# testv2.net
KiCad netlist of a schematic drawn in EAGLE
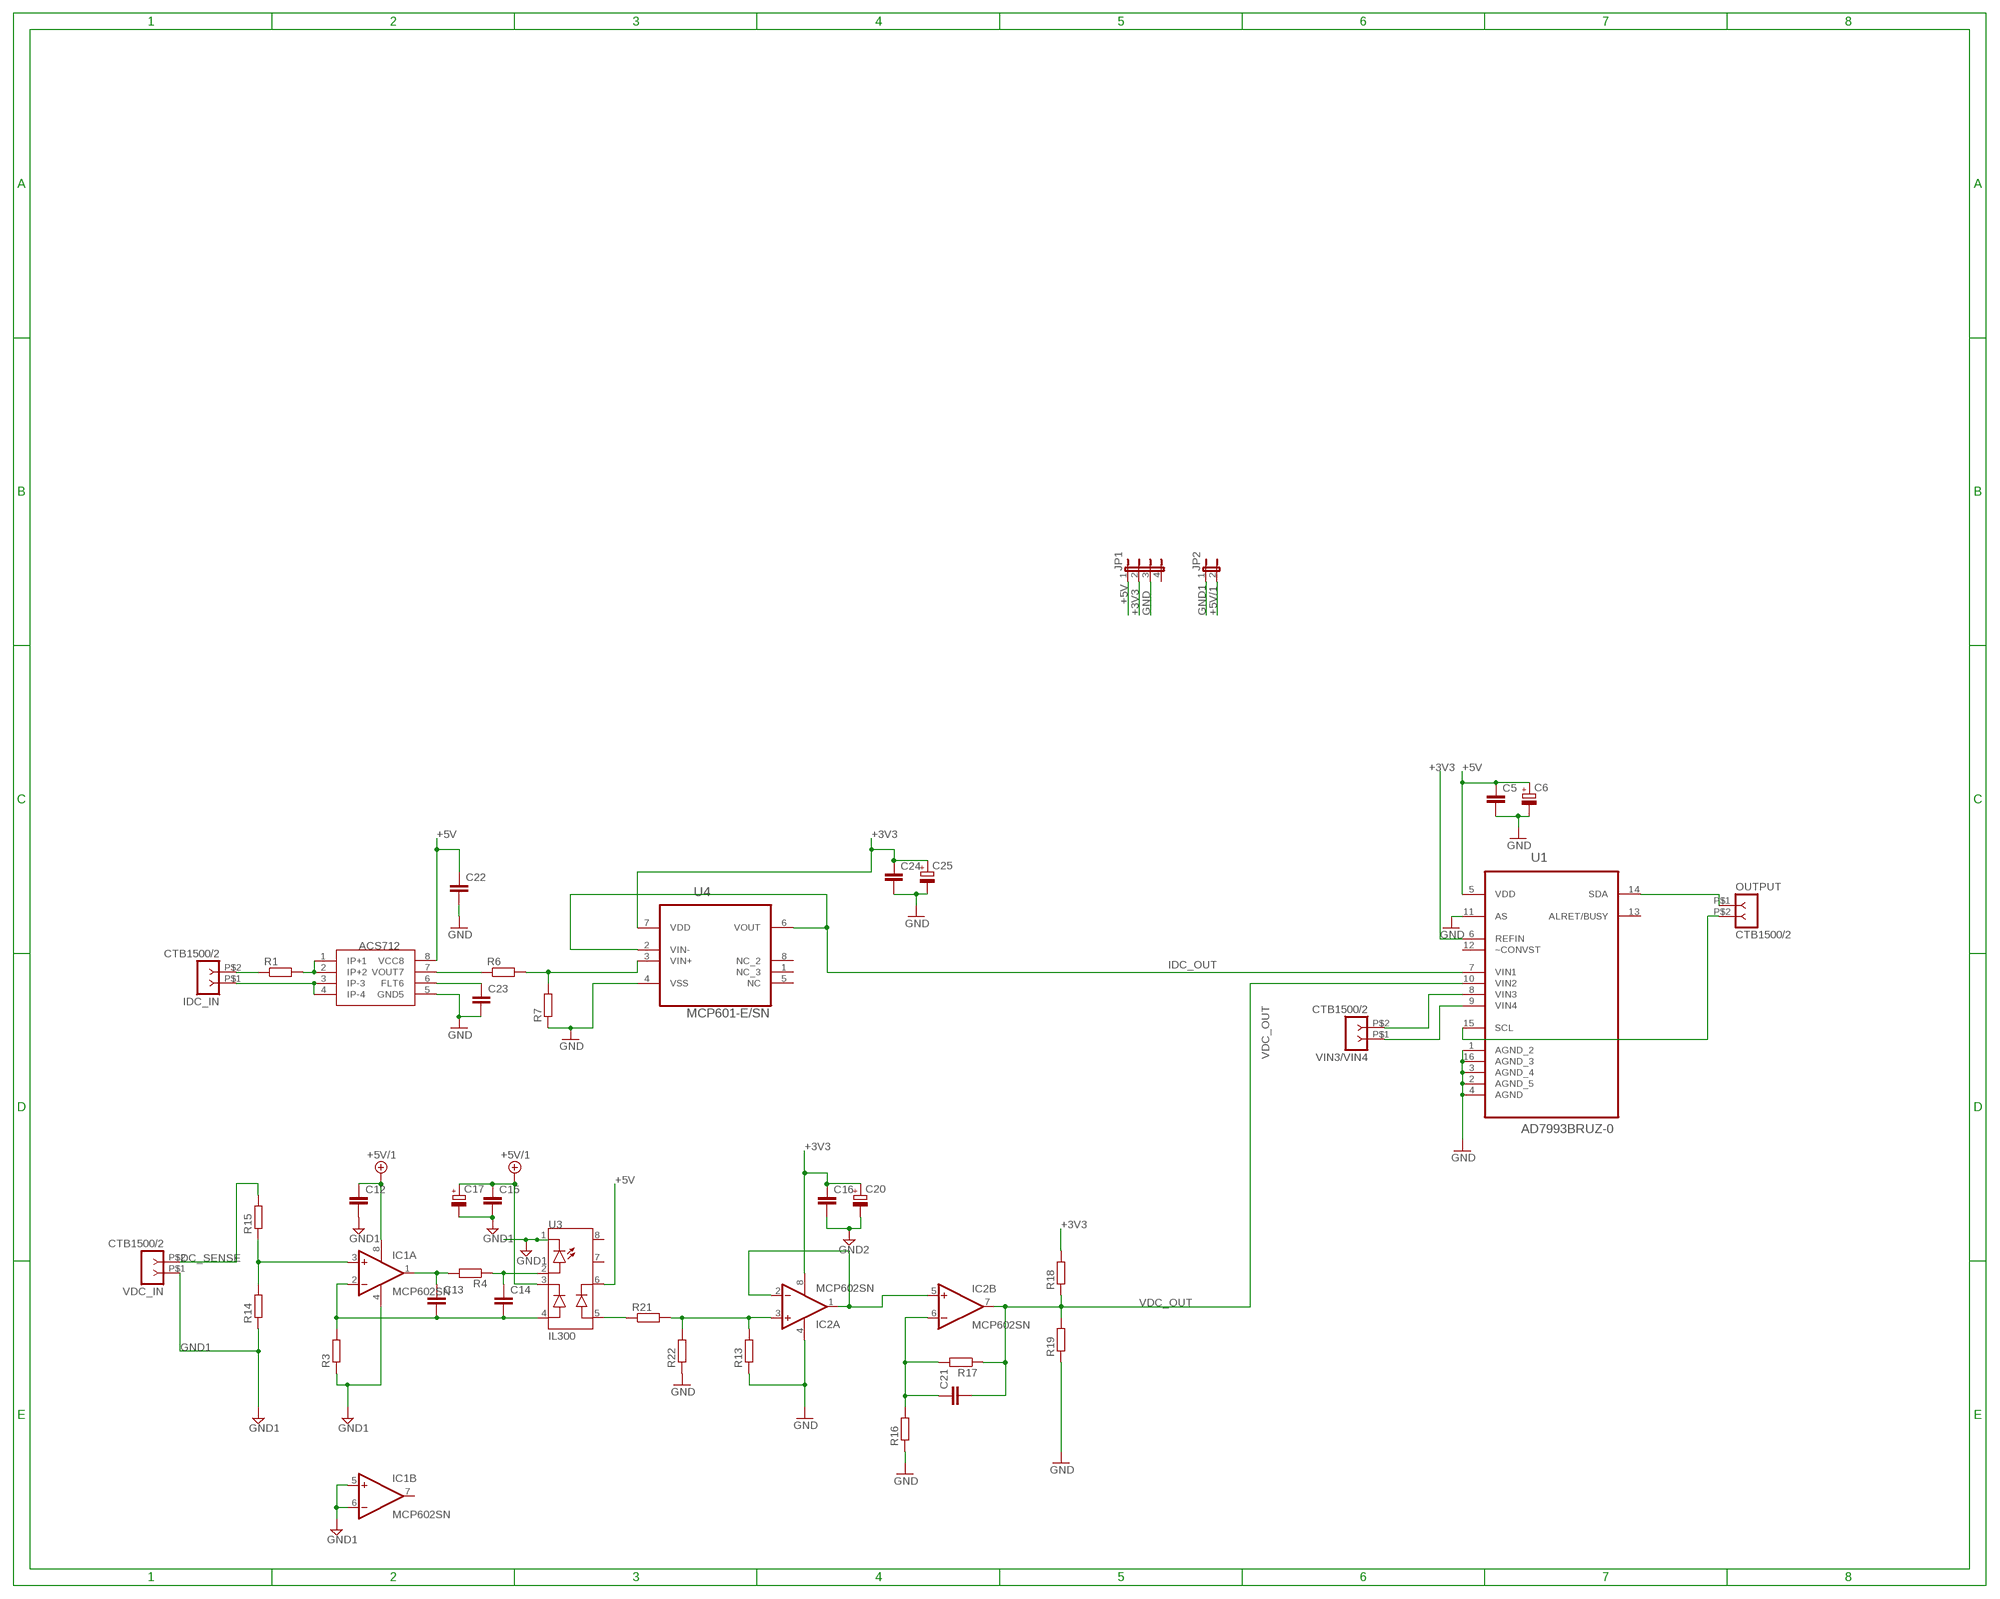
[diagram p0: schematic, sheet 1]

(export (version "E")
  (design (tool "Eeschema 10.0.6"))
  (components
    (comp (ref "C5")
      (value "C-EU025-025X050")
      (footprint "eagle-import:C025-025X050")
      (libsource (lib "eagle-import") (part "C-EU025-025X050"))
    )
    (comp (ref "C6")
      (value "CPOL-EUE2-4")
      (footprint "eagle-import:E2-4")
      (libsource (lib "eagle-import") (part "CPOL-EUE2-4"))
    )
    (comp (ref "C12")
      (value "C-EU025-025X050")
      (footprint "eagle-import:C025-025X050")
      (libsource (lib "eagle-import") (part "C-EU025-025X050"))
    )
    (comp (ref "C13")
      (value "C-EU025-025X050")
      (footprint "eagle-import:C025-025X050")
      (libsource (lib "eagle-import") (part "C-EU025-025X050"))
    )
    (comp (ref "C14")
      (value "C-EU025-025X050")
      (footprint "eagle-import:C025-025X050")
      (libsource (lib "eagle-import") (part "C-EU025-025X050"))
    )
    (comp (ref "C15")
      (value "C-EU025-025X050")
      (footprint "eagle-import:C025-025X050")
      (libsource (lib "eagle-import") (part "C-EU025-025X050"))
    )
    (comp (ref "C16")
      (value "C-EU025-025X050")
      (footprint "eagle-import:C025-025X050")
      (libsource (lib "eagle-import") (part "C-EU025-025X050"))
    )
    (comp (ref "C17")
      (value "CPOL-EUE2-4")
      (footprint "eagle-import:E2-4")
      (libsource (lib "eagle-import") (part "CPOL-EUE2-4"))
    )
    (comp (ref "C20")
      (value "CPOL-EUE2-4")
      (footprint "eagle-import:E2-4")
      (libsource (lib "eagle-import") (part "CPOL-EUE2-4"))
    )
    (comp (ref "C21")
      (value "C-EU025-025X050")
      (footprint "eagle-import:C025-025X050")
      (libsource (lib "eagle-import") (part "C-EU025-025X050"))
    )
    (comp (ref "C22")
      (value "C-EU025-025X050")
      (footprint "eagle-import:C025-025X050")
      (libsource (lib "eagle-import") (part "C-EU025-025X050"))
    )
    (comp (ref "C23")
      (value "C-EU025-025X050")
      (footprint "eagle-import:C025-025X050")
      (libsource (lib "eagle-import") (part "C-EU025-025X050"))
    )
    (comp (ref "C24")
      (value "C-EU025-025X050")
      (footprint "eagle-import:C025-025X050")
      (libsource (lib "eagle-import") (part "C-EU025-025X050"))
    )
    (comp (ref "C25")
      (value "CPOL-EUE2-4")
      (footprint "eagle-import:E2-4")
      (libsource (lib "eagle-import") (part "CPOL-EUE2-4"))
    )
    (comp (ref "IC1")
      (value "MCP602SN")
      (footprint "eagle-import:SO08")
      (libsource (lib "eagle-import") (part "MCP602SN"))
    )
    (comp (ref "IC2")
      (value "MCP602SN")
      (footprint "eagle-import:SO08")
      (libsource (lib "eagle-import") (part "MCP602SN"))
    )
    (comp (ref "IDC_IN")
      (value "CTB1500/2")
      (footprint "eagle-import:CTB1500-2")
      (libsource (lib "eagle-import") (part "CTB1500/2"))
    )
    (comp (ref "JP1")
      (value "JP4E")
      (footprint "eagle-import:JP4")
      (libsource (lib "eagle-import") (part "JP4E"))
    )
    (comp (ref "JP2")
      (value "JP1E")
      (footprint "eagle-import:JP1")
      (libsource (lib "eagle-import") (part "JP1E"))
    )
    (comp (ref "OUTPUT")
      (value "CTB1500/2")
      (footprint "eagle-import:CTB1500-2")
      (libsource (lib "eagle-import") (part "CTB1500/2"))
    )
    (comp (ref "R1")
      (value "R-EU_0207/7")
      (footprint "eagle-import:0207_7")
      (libsource (lib "eagle-import") (part "R-EU_0207/7"))
    )
    (comp (ref "R3")
      (value "R-EU_0207/7")
      (footprint "eagle-import:0207_7")
      (libsource (lib "eagle-import") (part "R-EU_0207/7"))
    )
    (comp (ref "R4")
      (value "R-EU_0207/7")
      (footprint "eagle-import:0207_7")
      (libsource (lib "eagle-import") (part "R-EU_0207/7"))
    )
    (comp (ref "R6")
      (value "R-EU_0207/7")
      (footprint "eagle-import:0207_7")
      (libsource (lib "eagle-import") (part "R-EU_0207/7"))
    )
    (comp (ref "R7")
      (value "R-EU_0207/7")
      (footprint "eagle-import:0207_7")
      (libsource (lib "eagle-import") (part "R-EU_0207/7"))
    )
    (comp (ref "R13")
      (value "R-EU_0207/7")
      (footprint "eagle-import:0207_7")
      (libsource (lib "eagle-import") (part "R-EU_0207/7"))
    )
    (comp (ref "R14")
      (value "R-EU_0207/7")
      (footprint "eagle-import:0207_7")
      (libsource (lib "eagle-import") (part "R-EU_0207/7"))
    )
    (comp (ref "R15")
      (value "R-EU_0207/7")
      (footprint "eagle-import:0207_7")
      (libsource (lib "eagle-import") (part "R-EU_0207/7"))
    )
    (comp (ref "R16")
      (value "R-EU_0207/7")
      (footprint "eagle-import:0207_7")
      (libsource (lib "eagle-import") (part "R-EU_0207/7"))
    )
    (comp (ref "R17")
      (value "R-EU_0207/7")
      (footprint "eagle-import:0207_7")
      (libsource (lib "eagle-import") (part "R-EU_0207/7"))
    )
    (comp (ref "R18")
      (value "R-EU_0207/7")
      (footprint "eagle-import:0207_7")
      (libsource (lib "eagle-import") (part "R-EU_0207/7"))
    )
    (comp (ref "R19")
      (value "R-EU_0207/7")
      (footprint "eagle-import:0207_7")
      (libsource (lib "eagle-import") (part "R-EU_0207/7"))
    )
    (comp (ref "R21")
      (value "R-EU_0207/7")
      (footprint "eagle-import:0207_7")
      (libsource (lib "eagle-import") (part "R-EU_0207/7"))
    )
    (comp (ref "R22")
      (value "R-EU_0207/7")
      (footprint "eagle-import:0207_7")
      (libsource (lib "eagle-import") (part "R-EU_0207/7"))
    )
    (comp (ref "U$10")
      (value "ACS712")
      (footprint "eagle-import:SOIC8")
      (libsource (lib "eagle-import") (part "ACS712"))
    )
    (comp (ref "U1")
      (value "AD7993BRUZ-0")
      (footprint "eagle-import:SOP65P640X120-16N")
      (libsource (lib "eagle-import") (part "AD7993BRUZ-0"))
    )
    (comp (ref "U3")
      (value "IL300")
      (footprint "eagle-import:SO8")
      (libsource (lib "eagle-import") (part "IL300"))
    )
    (comp (ref "U4")
      (value "MCP601-E/SN")
      (footprint "eagle-import:SOIC127P600X175-8N")
      (libsource (lib "eagle-import") (part "MCP601-E/SN"))
    )
    (comp (ref "VDC_IN")
      (value "CTB1500/2")
      (footprint "eagle-import:CTB1500-2")
      (libsource (lib "eagle-import") (part "CTB1500/2"))
    )
    (comp (ref "VIN3/VIN4")
      (value "CTB1500/2")
      (footprint "eagle-import:CTB1500-2")
      (libsource (lib "eagle-import") (part "CTB1500/2"))
    )
  )
  (nets
    (net (code "1") (name "+5V{slash}1") (class "Default")
      (node (ref "C12") (pin "1") (pinfunction "1_1") (pintype "passive"))
      (node (ref "C15") (pin "1") (pinfunction "1_1") (pintype "passive"))
      (node (ref "C17") (pin "+") (pinfunction "+_+") (pintype "passive"))
      (node (ref "IC1") (pin "8") (pinfunction "V+_8") (pintype "power_in"))
      (node (ref "JP2") (pin "2") (pinfunction "2_2") (pintype "passive"))
      (node (ref "U3") (pin "3") (pinfunction "C_FB_3") (pintype "passive"))
    )
    (net (code "2") (name "/+3V3") (class "Default")
      (node (ref "C16") (pin "1") (pinfunction "1_1") (pintype "passive"))
      (node (ref "C20") (pin "+") (pinfunction "+_+") (pintype "passive"))
      (node (ref "C24") (pin "1") (pinfunction "1_1") (pintype "passive"))
      (node (ref "C25") (pin "+") (pinfunction "+_+") (pintype "passive"))
      (node (ref "IC2") (pin "8") (pinfunction "V+_8") (pintype "power_in"))
      (node (ref "JP1") (pin "2") (pinfunction "2_2") (pintype "passive"))
      (node (ref "R18") (pin "2") (pinfunction "2_2") (pintype "passive"))
      (node (ref "U1") (pin "6") (pinfunction "REFIN_6") (pintype "input"))
      (node (ref "U4") (pin "7") (pinfunction "VDD_7") (pintype "power_in"))
    )
    (net (code "3") (name "/+5V") (class "Default")
      (node (ref "C22") (pin "1") (pinfunction "1_1") (pintype "passive"))
      (node (ref "C5") (pin "1") (pinfunction "1_1") (pintype "passive"))
      (node (ref "C6") (pin "+") (pinfunction "+_+") (pintype "passive"))
      (node (ref "JP1") (pin "1") (pinfunction "1_1") (pintype "passive"))
      (node (ref "U$10") (pin "8") (pinfunction "VCC8_8") (pintype "power_in"))
      (node (ref "U1") (pin "5") (pinfunction "VDD_5") (pintype "power_in"))
      (node (ref "U3") (pin "6") (pinfunction "C_OUT_6") (pintype "passive"))
    )
    (net (code "4") (name "/DC_SENSE") (class "Default")
      (node (ref "R15") (pin "2") (pinfunction "2_2") (pintype "passive"))
      (node (ref "VDC_IN") (pin "P$2") (pinfunction "2_P$2") (pintype "passive"))
    )
    (net (code "5") (name "/IDC_OUT") (class "Default")
      (node (ref "U1") (pin "7") (pinfunction "VIN1_7") (pintype "input"))
      (node (ref "U4") (pin "2") (pinfunction "VIN-_2") (pintype "input"))
      (node (ref "U4") (pin "6") (pinfunction "VOUT_6") (pintype "output"))
    )
    (net (code "6") (name "/VDC_OUT") (class "Default")
      (node (ref "C21") (pin "2") (pinfunction "2_2") (pintype "passive"))
      (node (ref "IC2") (pin "7") (pinfunction "OUT_7") (pintype "output"))
      (node (ref "R17") (pin "1") (pinfunction "1_1") (pintype "passive"))
      (node (ref "R18") (pin "1") (pinfunction "1_1") (pintype "passive"))
      (node (ref "R19") (pin "2") (pinfunction "2_2") (pintype "passive"))
      (node (ref "U1") (pin "10") (pinfunction "VIN2_10") (pintype "input"))
    )
    (net (code "7") (name "GND") (class "Default")
      (node (ref "C22") (pin "2") (pinfunction "2_2") (pintype "passive"))
      (node (ref "C23") (pin "2") (pinfunction "2_2") (pintype "passive"))
      (node (ref "C24") (pin "2") (pinfunction "2_2") (pintype "passive"))
      (node (ref "C25") (pin "-") (pinfunction "-_-") (pintype "passive"))
      (node (ref "C5") (pin "2") (pinfunction "2_2") (pintype "passive"))
      (node (ref "C6") (pin "-") (pinfunction "-_-") (pintype "passive"))
      (node (ref "IC2") (pin "4") (pinfunction "V-_4") (pintype "power_in"))
      (node (ref "JP1") (pin "3") (pinfunction "3_3") (pintype "passive"))
      (node (ref "R13") (pin "1") (pinfunction "1_1") (pintype "passive"))
      (node (ref "R16") (pin "1") (pinfunction "1_1") (pintype "passive"))
      (node (ref "R19") (pin "1") (pinfunction "1_1") (pintype "passive"))
      (node (ref "R22") (pin "1") (pinfunction "1_1") (pintype "passive"))
      (node (ref "R7") (pin "1") (pinfunction "1_1") (pintype "passive"))
      (node (ref "U$10") (pin "5") (pinfunction "GND5_5") (pintype "power_in"))
      (node (ref "U1") (pin "1") (pinfunction "AGND_2_1") (pintype "passive"))
      (node (ref "U1") (pin "11") (pinfunction "AS_11") (pintype "input"))
      (node (ref "U1") (pin "16") (pinfunction "AGND_3_16") (pintype "passive"))
      (node (ref "U1") (pin "2") (pinfunction "AGND_5_2") (pintype "passive"))
      (node (ref "U1") (pin "3") (pinfunction "AGND_4_3") (pintype "passive"))
      (node (ref "U1") (pin "4") (pinfunction "AGND_4") (pintype "passive"))
      (node (ref "U4") (pin "4") (pinfunction "VSS_4") (pintype "power_in"))
    )
    (net (code "8") (name "GND1") (class "Default")
      (node (ref "C12") (pin "2") (pinfunction "2_2") (pintype "passive"))
      (node (ref "C15") (pin "2") (pinfunction "2_2") (pintype "passive"))
      (node (ref "C17") (pin "-") (pinfunction "-_-") (pintype "passive"))
      (node (ref "IC1") (pin "4") (pinfunction "V-_4") (pintype "power_in"))
      (node (ref "IC1") (pin "5") (pinfunction "+IN_5") (pintype "input"))
      (node (ref "IC1") (pin "6") (pinfunction "-IN_6") (pintype "input"))
      (node (ref "JP2") (pin "1") (pinfunction "1_1") (pintype "passive"))
      (node (ref "R14") (pin "1") (pinfunction "1_1") (pintype "passive"))
      (node (ref "R3") (pin "1") (pinfunction "1_1") (pintype "passive"))
      (node (ref "U3") (pin "1") (pinfunction "C_LED_1") (pintype "passive"))
      (node (ref "VDC_IN") (pin "P$1") (pinfunction "1_P$1") (pintype "passive"))
    )
    (net (code "9") (name "GND2") (class "Default")
      (node (ref "C16") (pin "2") (pinfunction "2_2") (pintype "passive"))
      (node (ref "C20") (pin "-") (pinfunction "-_-") (pintype "passive"))
    )
    (net (code "10") (name "Net-(IC1A-+IN)") (class "Default")
      (node (ref "IC1") (pin "3") (pinfunction "+IN_3") (pintype "input"))
      (node (ref "R14") (pin "2") (pinfunction "2_2") (pintype "passive"))
      (node (ref "R15") (pin "1") (pinfunction "1_1") (pintype "passive"))
    )
    (net (code "11") (name "Net-(IC1A--IN)") (class "Default")
      (node (ref "C13") (pin "2") (pinfunction "2_2") (pintype "passive"))
      (node (ref "C14") (pin "2") (pinfunction "2_2") (pintype "passive"))
      (node (ref "IC1") (pin "2") (pinfunction "-IN_2") (pintype "input"))
      (node (ref "R3") (pin "2") (pinfunction "2_2") (pintype "passive"))
      (node (ref "U3") (pin "4") (pinfunction "A_FB_4") (pintype "passive"))
    )
    (net (code "12") (name "Net-(IC1A-OUT)") (class "Default")
      (node (ref "C13") (pin "1") (pinfunction "1_1") (pintype "passive"))
      (node (ref "IC1") (pin "1") (pinfunction "OUT_1") (pintype "output"))
      (node (ref "R4") (pin "2") (pinfunction "2_2") (pintype "passive"))
    )
    (net (code "13") (name "Net-(IC2A-+IN)") (class "Default")
      (node (ref "IC2") (pin "3") (pinfunction "+IN_3") (pintype "input"))
      (node (ref "R13") (pin "2") (pinfunction "2_2") (pintype "passive"))
      (node (ref "R21") (pin "2") (pinfunction "2_2") (pintype "passive"))
      (node (ref "R22") (pin "2") (pinfunction "2_2") (pintype "passive"))
    )
    (net (code "14") (name "Net-(IC2A--IN)") (class "Default")
      (node (ref "IC2") (pin "1") (pinfunction "OUT_1") (pintype "output"))
      (node (ref "IC2") (pin "2") (pinfunction "-IN_2") (pintype "input"))
      (node (ref "IC2") (pin "5") (pinfunction "+IN_5") (pintype "input"))
    )
    (net (code "15") (name "Net-(IC2B--IN)") (class "Default")
      (node (ref "C21") (pin "1") (pinfunction "1_1") (pintype "passive"))
      (node (ref "IC2") (pin "6") (pinfunction "-IN_6") (pintype "input"))
      (node (ref "R16") (pin "2") (pinfunction "2_2") (pintype "passive"))
      (node (ref "R17") (pin "2") (pinfunction "2_2") (pintype "passive"))
    )
    (net (code "16") (name "Net-(IDC_IN-1)") (class "Default")
      (node (ref "IDC_IN") (pin "P$1") (pinfunction "1_P$1") (pintype "passive"))
      (node (ref "U$10") (pin "3") (pinfunction "IP-3_3") (pintype "bidirectional"))
      (node (ref "U$10") (pin "4") (pinfunction "IP-4_4") (pintype "bidirectional"))
    )
    (net (code "17") (name "Net-(IDC_IN-2)") (class "Default")
      (node (ref "IDC_IN") (pin "P$2") (pinfunction "2_P$2") (pintype "passive"))
      (node (ref "R1") (pin "1") (pinfunction "1_1") (pintype "passive"))
    )
    (net (code "18") (name "Net-(OUTPUT-1)") (class "Default")
      (node (ref "OUTPUT") (pin "P$1") (pinfunction "1_P$1") (pintype "passive"))
      (node (ref "U1") (pin "14") (pinfunction "SDA_14") (pintype "bidirectional"))
    )
    (net (code "19") (name "Net-(OUTPUT-2)") (class "Default")
      (node (ref "OUTPUT") (pin "P$2") (pinfunction "2_P$2") (pintype "passive"))
      (node (ref "U1") (pin "15") (pinfunction "SCL_15") (pintype "input"))
    )
    (net (code "20") (name "Net-(U$10-FLT6)") (class "Default")
      (node (ref "C23") (pin "1") (pinfunction "1_1") (pintype "passive"))
      (node (ref "U$10") (pin "6") (pinfunction "FLT6_6") (pintype "passive"))
    )
    (net (code "21") (name "Net-(U$10-IP+1)") (class "Default")
      (node (ref "R1") (pin "2") (pinfunction "2_2") (pintype "passive"))
      (node (ref "U$10") (pin "1") (pinfunction "IP+1_1") (pintype "bidirectional"))
      (node (ref "U$10") (pin "2") (pinfunction "IP+2_2") (pintype "bidirectional"))
    )
    (net (code "22") (name "Net-(U$10-VOUT7)") (class "Default")
      (node (ref "R6") (pin "1") (pinfunction "1_1") (pintype "passive"))
      (node (ref "U$10") (pin "7") (pinfunction "VOUT7_7") (pintype "output"))
    )
    (net (code "23") (name "Net-(U1-VIN3)") (class "Default")
      (node (ref "U1") (pin "8") (pinfunction "VIN3_8") (pintype "input"))
      (node (ref "VIN3/VIN4") (pin "P$2") (pinfunction "2_P$2") (pintype "passive"))
    )
    (net (code "24") (name "Net-(U1-VIN4)") (class "Default")
      (node (ref "U1") (pin "9") (pinfunction "VIN4_9") (pintype "input"))
      (node (ref "VIN3/VIN4") (pin "P$1") (pinfunction "1_P$1") (pintype "passive"))
    )
    (net (code "25") (name "Net-(U3-A_LED)") (class "Default")
      (node (ref "C14") (pin "1") (pinfunction "1_1") (pintype "passive"))
      (node (ref "R4") (pin "1") (pinfunction "1_1") (pintype "passive"))
      (node (ref "U3") (pin "2") (pinfunction "A_LED_2") (pintype "passive"))
    )
    (net (code "26") (name "Net-(U3-A_OUT)") (class "Default")
      (node (ref "R21") (pin "1") (pinfunction "1_1") (pintype "passive"))
      (node (ref "U3") (pin "5") (pinfunction "A_OUT_5") (pintype "passive"))
    )
    (net (code "27") (name "Net-(U4-VIN+)") (class "Default")
      (node (ref "R6") (pin "2") (pinfunction "2_2") (pintype "passive"))
      (node (ref "R7") (pin "2") (pinfunction "2_2") (pintype "passive"))
      (node (ref "U4") (pin "3") (pinfunction "VIN+_3") (pintype "input"))
    )
    (net (code "28") (name "unconnected-(IC1B-OUT-Pad7)") (class "Default")
      (node (ref "IC1") (pin "7") (pinfunction "OUT_7") (pintype "output"))
    )
    (net (code "29") (name "unconnected-(JP1-Pad4)") (class "Default")
      (node (ref "JP1") (pin "4") (pinfunction "4_4") (pintype "passive"))
    )
    (net (code "30") (name "unconnected-(U1-ALRET{slash}BUSY-Pad13)") (class "Default")
      (node (ref "U1") (pin "13") (pinfunction "ALRET/BUSY_13") (pintype "output"))
    )
    (net (code "31") (name "unconnected-(U1-~{CONVST}-Pad12)") (class "Default")
      (node (ref "U1") (pin "12") (pinfunction "~{CONVST}_12") (pintype "input"))
    )
    (net (code "32") (name "unconnected-(U3-PIN7-Pad7)") (class "Default")
      (node (ref "U3") (pin "7") (pinfunction "PIN7_7") (pintype "no_connect"))
    )
    (net (code "33") (name "unconnected-(U3-PIN8-Pad8)") (class "Default")
      (node (ref "U3") (pin "8") (pinfunction "PIN8_8") (pintype "no_connect"))
    )
    (net (code "34") (name "unconnected-(U4-NC-Pad5)") (class "Default")
      (node (ref "U4") (pin "5") (pinfunction "NC_5") (pintype "no_connect"))
    )
    (net (code "35") (name "unconnected-(U4-NC_2-Pad8)") (class "Default")
      (node (ref "U4") (pin "8") (pinfunction "NC_2_8") (pintype "no_connect"))
    )
    (net (code "36") (name "unconnected-(U4-NC_3-Pad1)") (class "Default")
      (node (ref "U4") (pin "1") (pinfunction "NC_3_1") (pintype "no_connect"))
    )
  )
)
